# TP18mm.net
KiCad netlist of a schematic drawn in EAGLE
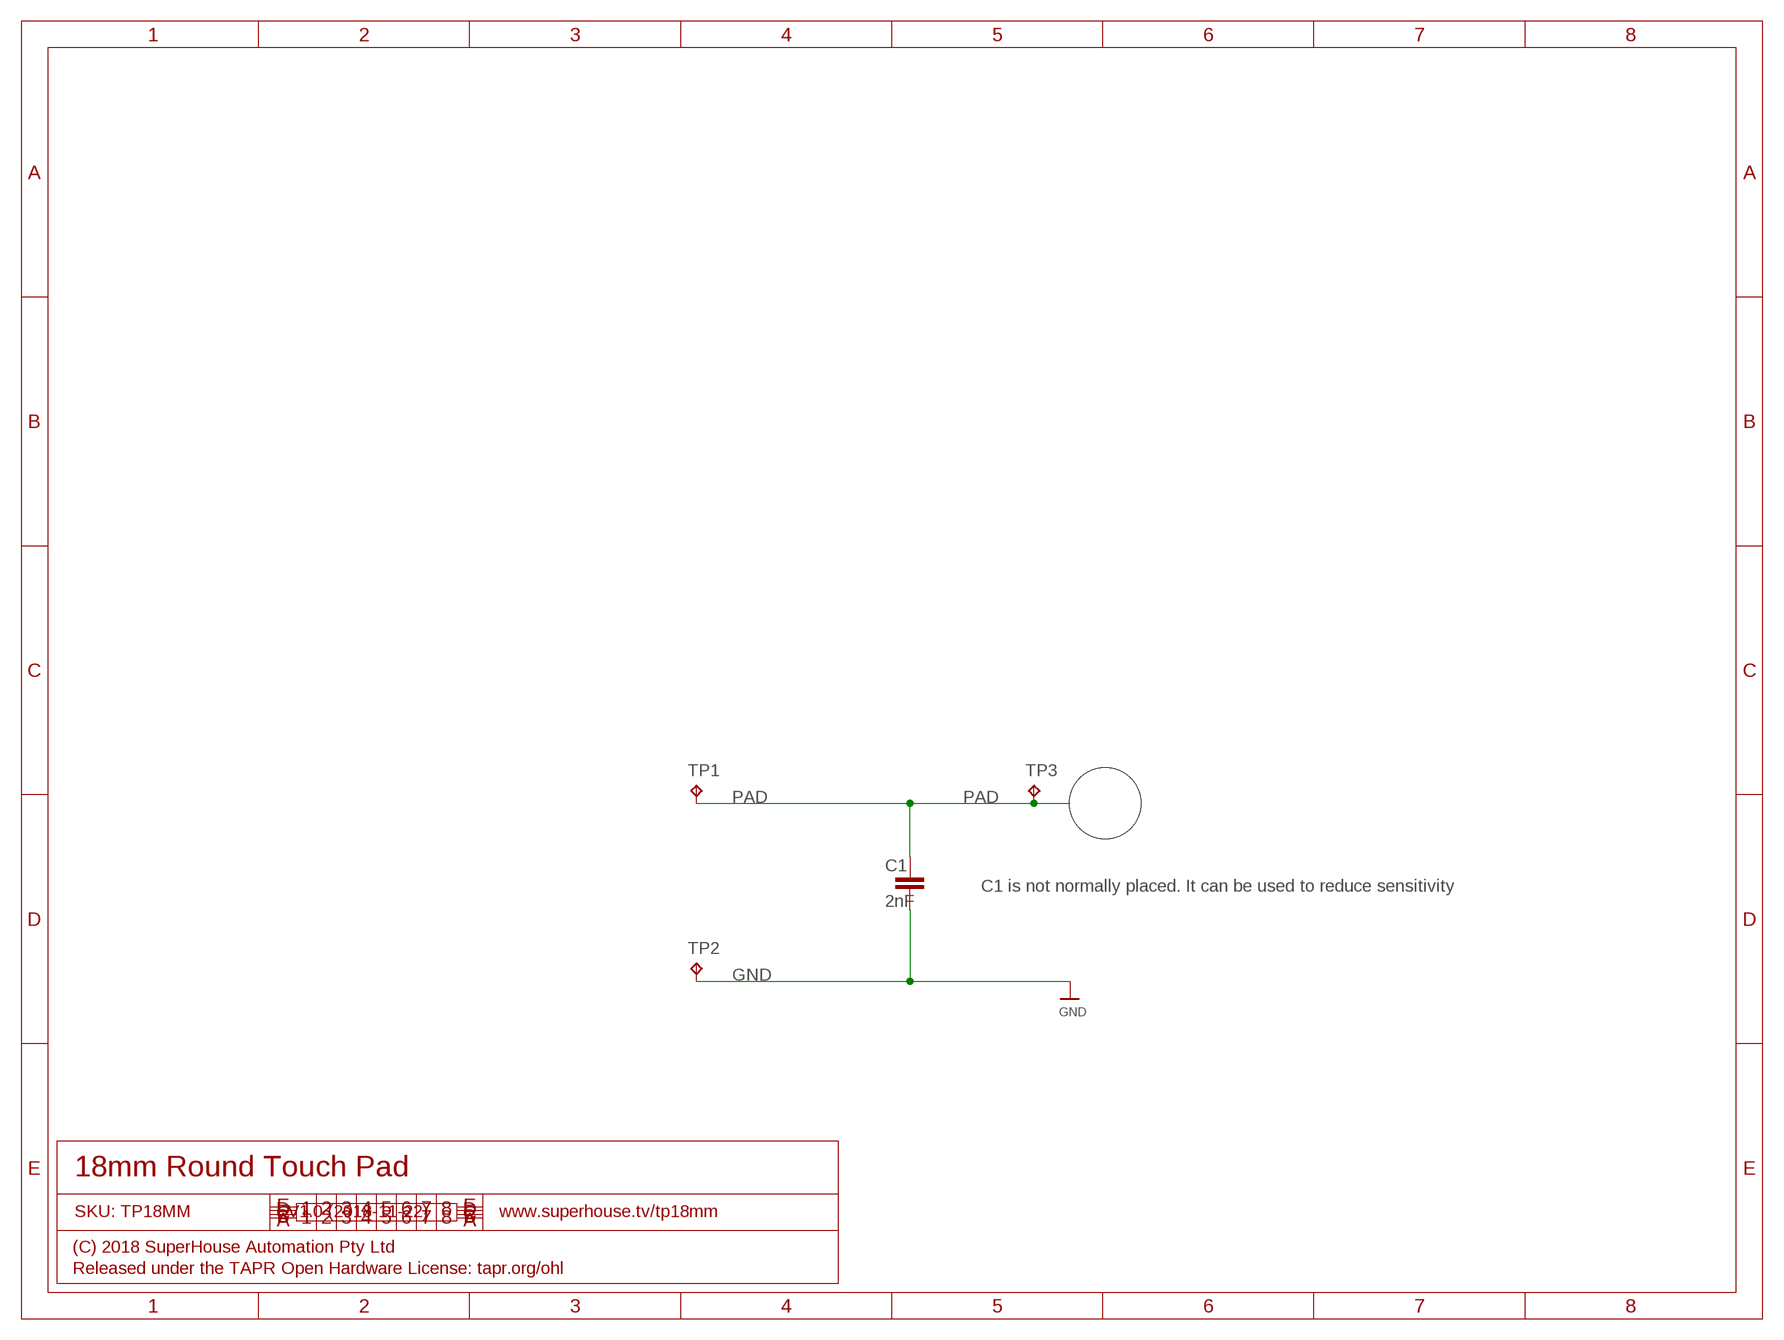
[diagram p0: schematic, sheet 1]

(export (version "E")
  (design (tool "Eeschema 10.0.6"))
  (components
    (comp (ref "C1")
      (value "2nF")
      (footprint "eagle-import:0603")
      (libsource (lib "eagle-import") (part "CAP0603"))
    )
    (comp (ref "TP1")
      (value "TPB2,54")
      (footprint "eagle-import:B2,54")
      (libsource (lib "eagle-import") (part "TPB2,54"))
    )
    (comp (ref "TP2")
      (value "TPB2,54")
      (footprint "eagle-import:B2,54")
      (libsource (lib "eagle-import") (part "TPB2,54"))
    )
    (comp (ref "TP3")
      (value "TPB2,54")
      (footprint "eagle-import:B2,54")
      (libsource (lib "eagle-import") (part "TPB2,54"))
    )
  )
  (nets
    (net (code "1") (name "/PAD") (class "Default")
      (node (ref "C1") (pin "1") (pinfunction "1_1") (pintype "passive"))
      (node (ref "TP1") (pin "TP") (pinfunction "TP_TP") (pintype "input"))
      (node (ref "TP3") (pin "TP") (pinfunction "TP_TP") (pintype "input"))
    )
    (net (code "2") (name "GND") (class "Default")
      (node (ref "C1") (pin "2") (pinfunction "2_2") (pintype "passive"))
      (node (ref "TP2") (pin "TP") (pinfunction "TP_TP") (pintype "input"))
    )
  )
)
